# ARDUINO_3V_TTL_INTERFACE_2_PI.net
KiCad netlist of a schematic drawn in EAGLE
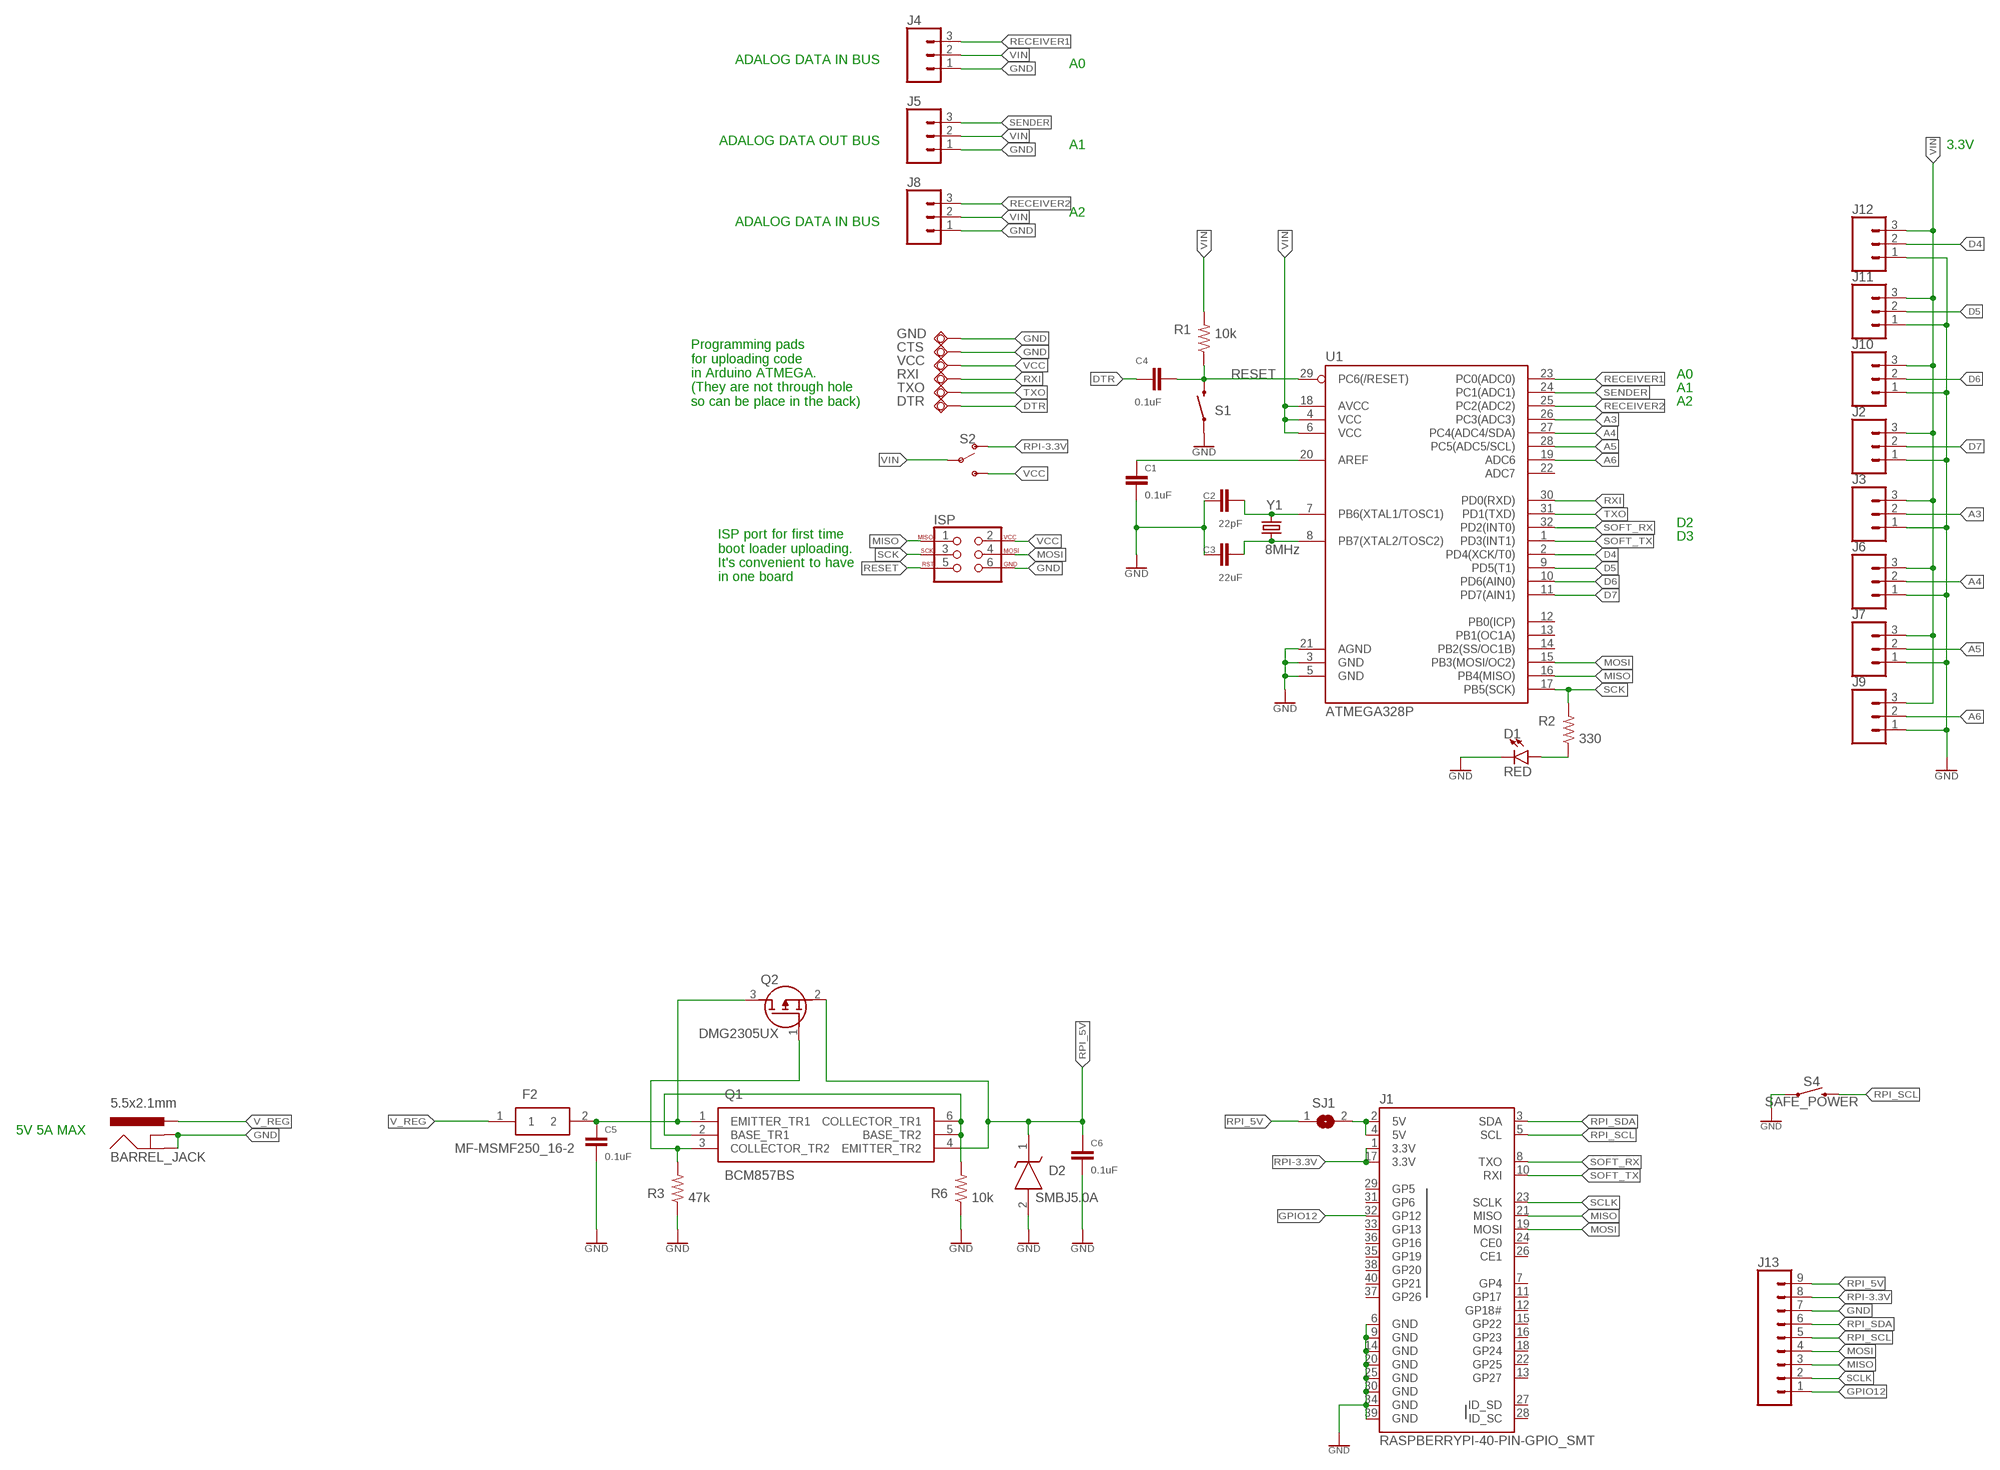
[diagram p0: schematic, sheet 1]

(export (version "E")
  (design (tool "Eeschema 10.0.6"))
  (components
    (comp (ref "BARREL_JACK")
      (value "5.5x2.1mm")
      (footprint "eagle-import:POWER_JACK_SMD")
      (libsource (lib "eagle-import") (part "POWER_JACKSMD"))
    )
    (comp (ref "C1")
      (value "0.1uF")
      (footprint "eagle-import:0603")
      (libsource (lib "eagle-import") (part "0.1UF-0603-100V-10%"))
    )
    (comp (ref "C2")
      (value "22pF")
      (footprint "eagle-import:0603")
      (libsource (lib "eagle-import") (part "0.1UF-0603-100V-10%"))
    )
    (comp (ref "C3")
      (value "22uF")
      (footprint "eagle-import:0603")
      (libsource (lib "eagle-import") (part "0.1UF-0603-100V-10%"))
    )
    (comp (ref "C4")
      (value "0.1uF")
      (footprint "eagle-import:0603")
      (libsource (lib "eagle-import") (part "0.1UF-0603-100V-10%"))
    )
    (comp (ref "C5")
      (value "0.1uF")
      (footprint "eagle-import:0603")
      (libsource (lib "eagle-import") (part "0.1UF-0603-100V-10%"))
    )
    (comp (ref "C6")
      (value "0.1uF")
      (footprint "eagle-import:0603")
      (libsource (lib "eagle-import") (part "0.1UF-0603-100V-10%"))
    )
    (comp (ref "CTS")
      (value "TPSQB1,27")
      (footprint "eagle-import:B1,27")
      (libsource (lib "eagle-import") (part "TPSQB1,27"))
    )
    (comp (ref "D1")
      (value "RED")
      (footprint "eagle-import:LED-0603")
      (libsource (lib "eagle-import") (part "LED-GREEN0603"))
    )
    (comp (ref "D2")
      (value "SMBJ5.0A")
      (footprint "eagle-import:DIOM5436X244N")
      (fields
        (field (name "MANUFACTURER_PART_NUMBER") "SMBJ5.0A-E3/52")
        (field (name "MOUSER_PART_NUMBER") "625-SMBJ5.0A-E3")
        (field (name "RS_PART_NUMBER") "1652507")
      )
      (libsource (lib "eagle-import") (part "SMBJ5.0A-E3_52"))
    )
    (comp (ref "DTR")
      (value "TPSQB1,27")
      (footprint "eagle-import:B1,27")
      (libsource (lib "eagle-import") (part "TPSQB1,27"))
    )
    (comp (ref "F2")
      (value "MF-MSMF250_16-2")
      (footprint "eagle-import:FUSC4632X160N")
      (fields
        (field (name "MANUFACTURER_PART_NUMBER") "MF-MSMF250/16-2")
        (field (name "MOUSER_PART_NUMBER") "652-MF-MSMF250/16-2")
      )
      (libsource (lib "eagle-import") (part "MF-MSMF250_16-2"))
    )
    (comp (ref "GND")
      (value "TPSQB1,27")
      (footprint "eagle-import:B1,27")
      (libsource (lib "eagle-import") (part "TPSQB1,27"))
    )
    (comp (ref "ISP")
      (value "AVR_SPI_PROG_3X2NS")
      (footprint "eagle-import:2X3-NS")
      (libsource (lib "eagle-import") (part "AVR_SPI_PROG_3X2NS"))
    )
    (comp (ref "J1")
      (value "RASPBERRYPI-40-PIN-GPIO_SMT")
      (footprint "eagle-import:2X20_SHROUDED_SMT")
      (libsource (lib "eagle-import") (part "RASPBERRYPI-40-PIN-GPIO_SMT"))
    )
    (comp (ref "J2")
      (value "CONN_03")
      (footprint "eagle-import:1X03")
      (libsource (lib "eagle-import") (part "CONN_03"))
    )
    (comp (ref "J3")
      (value "CONN_03")
      (footprint "eagle-import:1X03")
      (libsource (lib "eagle-import") (part "CONN_03"))
    )
    (comp (ref "J4")
      (value "CONN_03SMD")
      (footprint "eagle-import:1X03-1MM-RA")
      (libsource (lib "eagle-import") (part "CONN_03SMD"))
    )
    (comp (ref "J5")
      (value "CONN_03SMD")
      (footprint "eagle-import:1X03-1MM-RA")
      (libsource (lib "eagle-import") (part "CONN_03SMD"))
    )
    (comp (ref "J6")
      (value "CONN_03")
      (footprint "eagle-import:1X03")
      (libsource (lib "eagle-import") (part "CONN_03"))
    )
    (comp (ref "J7")
      (value "CONN_03")
      (footprint "eagle-import:1X03")
      (libsource (lib "eagle-import") (part "CONN_03"))
    )
    (comp (ref "J8")
      (value "CONN_03SMD")
      (footprint "eagle-import:1X03-1MM-RA")
      (libsource (lib "eagle-import") (part "CONN_03SMD"))
    )
    (comp (ref "J9")
      (value "CONN_03")
      (footprint "eagle-import:1X03")
      (libsource (lib "eagle-import") (part "CONN_03"))
    )
    (comp (ref "J10")
      (value "CONN_03")
      (footprint "eagle-import:1X03")
      (libsource (lib "eagle-import") (part "CONN_03"))
    )
    (comp (ref "J11")
      (value "CONN_03")
      (footprint "eagle-import:1X03")
      (libsource (lib "eagle-import") (part "CONN_03"))
    )
    (comp (ref "J12")
      (value "CONN_03")
      (footprint "eagle-import:1X03")
      (libsource (lib "eagle-import") (part "CONN_03"))
    )
    (comp (ref "J13")
      (value "CONN_09")
      (footprint "eagle-import:1X09")
      (libsource (lib "eagle-import") (part "CONN_09"))
    )
    (comp (ref "Q1")
      (value "BCM857BS")
      (footprint "eagle-import:SOT65P210X110-6N")
      (libsource (lib "eagle-import") (part "BCM857BS"))
    )
    (comp (ref "Q2")
      (value "DMG2305UX")
      (footprint "eagle-import:SOT96P240X102-3N")
      (fields
        (field (name "MANUFACTURER_PART_NUMBER") "DMG2305UXQ-7")
        (field (name "MOUSER_PART_NUMBER") "621-DMG2305UXQ-7")
      )
      (libsource (lib "eagle-import") (part "DMG2305UXQ-7"))
    )
    (comp (ref "R1")
      (value "10k")
      (footprint "eagle-import:0603")
      (libsource (lib "eagle-import") (part "10KOHM-0603-1/10W-1%"))
    )
    (comp (ref "R2")
      (value "330")
      (footprint "eagle-import:0603")
      (libsource (lib "eagle-import") (part "10KOHM-0603-1/10W-1%"))
    )
    (comp (ref "R3")
      (value "47k")
      (footprint "eagle-import:0603")
      (libsource (lib "eagle-import") (part "10KOHM-0603-1/10W-1%"))
    )
    (comp (ref "R6")
      (value "10k")
      (footprint "eagle-import:0603")
      (libsource (lib "eagle-import") (part "10KOHM-0603-1/10W-1%"))
    )
    (comp (ref "RXI")
      (value "TPSQB1,27")
      (footprint "eagle-import:B1,27")
      (libsource (lib "eagle-import") (part "TPSQB1,27"))
    )
    (comp (ref "S1")
      (value "RESET")
      (footprint "eagle-import:TACTILE_SWITCH_SMD_4.6X2.8MM")
      (libsource (lib "eagle-import") (part "MOMENTARY-SWITCH-SPST-SMD-4.6X2.8MM"))
    )
    (comp (ref "S2")
      (value "SWITCH-SPDT-SMD-RIGHT-ANGLE")
      (footprint "eagle-import:SWITCH_SPST_SMD_A")
      (libsource (lib "eagle-import") (part "SWITCH-SPDT-SMD-RIGHT-ANGLE"))
    )
    (comp (ref "S4")
      (value "SAFE_POWER")
      (footprint "eagle-import:TACTILE_SWITCH_PTH_12MM")
      (libsource (lib "eagle-import") (part "MOMENTARY-SWITCH-SPST-PTH-12MM"))
    )
    (comp (ref "SJ1") (value "SJ") (footprint "eagle-import:SJ") (libsource (lib "eagle-import") (part "SJ")))
    (comp (ref "TXO")
      (value "TPSQB1,27")
      (footprint "eagle-import:B1,27")
      (libsource (lib "eagle-import") (part "TPSQB1,27"))
    )
    (comp (ref "U1")
      (value "ATMEGA328P")
      (footprint "eagle-import:TQFP32-08")
      (libsource (lib "eagle-import") (part "ATMEGA328P_TQFP"))
    )
    (comp (ref "VCC")
      (value "TPSQB1,27")
      (footprint "eagle-import:B1,27")
      (libsource (lib "eagle-import") (part "TPSQB1,27"))
    )
    (comp (ref "Y1")
      (value "8MHz")
      (footprint "eagle-import:HC49UP")
      (libsource (lib "eagle-import") (part "CRYSTAL-8MHZSMD-HC49UP"))
    )
  )
  (nets
    (net (code "1") (name "A3") (class "Default")
      (node (ref "J3") (pin "2") (pinfunction "2_2") (pintype "passive"))
      (node (ref "U1") (pin "26") (pinfunction "PC3(ADC3)_26") (pintype "bidirectional"))
    )
    (net (code "2") (name "A4") (class "Default")
      (node (ref "J6") (pin "2") (pinfunction "2_2") (pintype "passive"))
      (node (ref "U1") (pin "27") (pinfunction "PC4(ADC4/SDA)_27") (pintype "bidirectional"))
    )
    (net (code "3") (name "A5") (class "Default")
      (node (ref "J7") (pin "2") (pinfunction "2_2") (pintype "passive"))
      (node (ref "U1") (pin "28") (pinfunction "PC5(ADC5/SCL)_28") (pintype "bidirectional"))
    )
    (net (code "4") (name "A6") (class "Default")
      (node (ref "J9") (pin "2") (pinfunction "2_2") (pintype "passive"))
      (node (ref "U1") (pin "19") (pinfunction "ADC6_19") (pintype "bidirectional"))
    )
    (net (code "5") (name "D4") (class "Default")
      (node (ref "J12") (pin "2") (pinfunction "2_2") (pintype "passive"))
      (node (ref "U1") (pin "2") (pinfunction "PD4(XCK/T0)_2") (pintype "bidirectional"))
    )
    (net (code "6") (name "D5") (class "Default")
      (node (ref "J11") (pin "2") (pinfunction "2_2") (pintype "passive"))
      (node (ref "U1") (pin "9") (pinfunction "PD5(T1)_9") (pintype "bidirectional"))
    )
    (net (code "7") (name "D6") (class "Default")
      (node (ref "J10") (pin "2") (pinfunction "2_2") (pintype "passive"))
      (node (ref "U1") (pin "10") (pinfunction "PD6(AIN0)_10") (pintype "bidirectional"))
    )
    (net (code "8") (name "D7") (class "Default")
      (node (ref "J2") (pin "2") (pinfunction "2_2") (pintype "passive"))
      (node (ref "U1") (pin "11") (pinfunction "PD7(AIN1)_11") (pintype "bidirectional"))
    )
    (net (code "9") (name "DTR") (class "Default")
      (node (ref "C4") (pin "1") (pinfunction "1_1") (pintype "passive"))
      (node (ref "DTR") (pin "TP") (pinfunction "TP_TP") (pintype "input"))
    )
    (net (code "10") (name "GND") (class "Default")
      (node (ref "BARREL_JACK") (pin "GND") (pinfunction "GNDBREAK_GND") (pintype "bidirectional"))
      (node (ref "BARREL_JACK") (pin "P$4") (pinfunction "GND_P$4") (pintype "bidirectional"))
      (node (ref "C1") (pin "2") (pinfunction "2_2") (pintype "passive"))
      (node (ref "C2") (pin "1") (pinfunction "1_1") (pintype "passive"))
      (node (ref "C3") (pin "1") (pinfunction "1_1") (pintype "passive"))
      (node (ref "C5") (pin "2") (pinfunction "2_2") (pintype "passive"))
      (node (ref "C6") (pin "2") (pinfunction "2_2") (pintype "passive"))
      (node (ref "CTS") (pin "TP") (pinfunction "TP_TP") (pintype "input"))
      (node (ref "D1") (pin "C") (pinfunction "C_C") (pintype "passive"))
      (node (ref "D2") (pin "2") (pinfunction "A_2") (pintype "bidirectional"))
      (node (ref "GND") (pin "TP") (pinfunction "TP_TP") (pintype "input"))
      (node (ref "ISP") (pin "6") (pinfunction "6_6") (pintype "passive"))
      (node (ref "J1") (pin "14") (pinfunction "GND_14") (pintype "power_in"))
      (node (ref "J1") (pin "20") (pinfunction "GND_20") (pintype "power_in"))
      (node (ref "J1") (pin "25") (pinfunction "GND_25") (pintype "power_in"))
      (node (ref "J1") (pin "30") (pinfunction "GND_30") (pintype "power_in"))
      (node (ref "J1") (pin "34") (pinfunction "GND_34") (pintype "power_in"))
      (node (ref "J1") (pin "39") (pinfunction "GND_39") (pintype "power_in"))
      (node (ref "J1") (pin "6") (pinfunction "GND_6") (pintype "power_in"))
      (node (ref "J1") (pin "9") (pinfunction "GND_9") (pintype "power_in"))
      (node (ref "J10") (pin "1") (pinfunction "1_1") (pintype "passive"))
      (node (ref "J11") (pin "1") (pinfunction "1_1") (pintype "passive"))
      (node (ref "J12") (pin "1") (pinfunction "1_1") (pintype "passive"))
      (node (ref "J13") (pin "7") (pinfunction "7_7") (pintype "passive"))
      (node (ref "J2") (pin "1") (pinfunction "1_1") (pintype "passive"))
      (node (ref "J3") (pin "1") (pinfunction "1_1") (pintype "passive"))
      (node (ref "J4") (pin "1") (pinfunction "1_1") (pintype "passive"))
      (node (ref "J5") (pin "1") (pinfunction "1_1") (pintype "passive"))
      (node (ref "J6") (pin "1") (pinfunction "1_1") (pintype "passive"))
      (node (ref "J7") (pin "1") (pinfunction "1_1") (pintype "passive"))
      (node (ref "J8") (pin "1") (pinfunction "1_1") (pintype "passive"))
      (node (ref "J9") (pin "1") (pinfunction "1_1") (pintype "passive"))
      (node (ref "R3") (pin "1") (pinfunction "1_1") (pintype "passive"))
      (node (ref "R6") (pin "1") (pinfunction "1_1") (pintype "passive"))
      (node (ref "S1") (pin "1") (pinfunction "1_1") (pintype "passive"))
      (node (ref "S1") (pin "2") (pinfunction "1_2") (pintype "passive"))
      (node (ref "S4") (pin "1") (pinfunction "1_1") (pintype "passive"))
      (node (ref "U1") (pin "21") (pinfunction "AGND_21") (pintype "bidirectional"))
      (node (ref "U1") (pin "3") (pinfunction "GND_3") (pintype "bidirectional"))
      (node (ref "U1") (pin "5") (pinfunction "GND_5") (pintype "bidirectional"))
    )
    (net (code "11") (name "GPIO12") (class "Default")
      (node (ref "J1") (pin "32") (pinfunction "GP12_32") (pintype "bidirectional"))
      (node (ref "J13") (pin "1") (pinfunction "1_1") (pintype "passive"))
    )
    (net (code "12") (name "MISO") (class "Default")
      (node (ref "ISP") (pin "1") (pinfunction "1_1") (pintype "passive"))
      (node (ref "J1") (pin "21") (pinfunction "MISO_21") (pintype "input"))
      (node (ref "J13") (pin "3") (pinfunction "3_3") (pintype "passive"))
      (node (ref "U1") (pin "16") (pinfunction "PB4(MISO)_16") (pintype "bidirectional"))
    )
    (net (code "13") (name "MOSI") (class "Default")
      (node (ref "ISP") (pin "4") (pinfunction "4_4") (pintype "passive"))
      (node (ref "J1") (pin "19") (pinfunction "MOSI_19") (pintype "output"))
      (node (ref "J13") (pin "4") (pinfunction "4_4") (pintype "passive"))
      (node (ref "U1") (pin "15") (pinfunction "PB3(MOSI/OC2)_15") (pintype "bidirectional"))
    )
    (net (code "14") (name "Net-(D1-PadA)") (class "Default")
      (node (ref "D1") (pin "A") (pinfunction "A_A") (pintype "passive"))
      (node (ref "R2") (pin "1") (pinfunction "1_1") (pintype "passive"))
    )
    (net (code "15") (name "Net-(J1-5V-Pad2)") (class "Default")
      (node (ref "J1") (pin "2") (pinfunction "5V_2") (pintype "power_in"))
      (node (ref "J1") (pin "4") (pinfunction "5V_4") (pintype "power_in"))
      (node (ref "SJ1") (pin "2") (pinfunction "2_2") (pintype "passive"))
    )
    (net (code "16") (name "Net-(Q1-BASE_TR1)") (class "Default")
      (node (ref "Q1") (pin "2") (pinfunction "BASE_TR1_2") (pintype "bidirectional"))
      (node (ref "Q1") (pin "5") (pinfunction "BASE_TR2_5") (pintype "bidirectional"))
      (node (ref "Q1") (pin "6") (pinfunction "COLLECTOR_TR1_6") (pintype "bidirectional"))
      (node (ref "R6") (pin "2") (pinfunction "2_2") (pintype "passive"))
    )
    (net (code "17") (name "Net-(Q1-COLLECTOR_TR2)") (class "Default")
      (node (ref "Q1") (pin "3") (pinfunction "COLLECTOR_TR2_3") (pintype "bidirectional"))
      (node (ref "Q2") (pin "1") (pinfunction "G_1") (pintype "input"))
      (node (ref "R3") (pin "2") (pinfunction "2_2") (pintype "passive"))
    )
    (net (code "18") (name "Net-(U1-AREF)") (class "Default")
      (node (ref "C1") (pin "1") (pinfunction "1_1") (pintype "passive"))
      (node (ref "U1") (pin "20") (pinfunction "AREF_20") (pintype "bidirectional"))
    )
    (net (code "19") (name "Net-(U1-PB6(XTAL1{slash}TOSC1))") (class "Default")
      (node (ref "C2") (pin "2") (pinfunction "2_2") (pintype "passive"))
      (node (ref "U1") (pin "7") (pinfunction "PB6(XTAL1/TOSC1)_7") (pintype "bidirectional"))
      (node (ref "Y1") (pin "2") (pinfunction "2_2") (pintype "passive"))
    )
    (net (code "20") (name "Net-(U1-PB7(XTAL2{slash}TOSC2))") (class "Default")
      (node (ref "C3") (pin "2") (pinfunction "2_2") (pintype "passive"))
      (node (ref "U1") (pin "8") (pinfunction "PB7(XTAL2/TOSC2)_8") (pintype "bidirectional"))
      (node (ref "Y1") (pin "1") (pinfunction "1_1") (pintype "passive"))
    )
    (net (code "21") (name "RECEIVER1") (class "Default")
      (node (ref "J4") (pin "3") (pinfunction "3_3") (pintype "passive"))
      (node (ref "U1") (pin "23") (pinfunction "PC0(ADC0)_23") (pintype "bidirectional"))
    )
    (net (code "22") (name "RECEIVER2") (class "Default")
      (node (ref "J8") (pin "3") (pinfunction "3_3") (pintype "passive"))
      (node (ref "U1") (pin "25") (pinfunction "PC2(ADC2)_25") (pintype "bidirectional"))
    )
    (net (code "23") (name "RESET") (class "Default")
      (node (ref "C4") (pin "2") (pinfunction "2_2") (pintype "passive"))
      (node (ref "ISP") (pin "5") (pinfunction "5_5") (pintype "passive"))
      (node (ref "R1") (pin "1") (pinfunction "1_1") (pintype "passive"))
      (node (ref "S1") (pin "3") (pinfunction "2_3") (pintype "passive"))
      (node (ref "S1") (pin "4") (pinfunction "2_4") (pintype "passive"))
      (node (ref "U1") (pin "29") (pinfunction "PC6(/RESET)_29") (pintype "bidirectional"))
    )
    (net (code "24") (name "RPI-3.3V") (class "Default")
      (node (ref "J1") (pin "1") (pinfunction "3.3V_1") (pintype "power_in"))
      (node (ref "J1") (pin "17") (pinfunction "3.3V_17") (pintype "power_in"))
      (node (ref "J13") (pin "8") (pinfunction "8_8") (pintype "passive"))
      (node (ref "S2") (pin "1") (pinfunction "O_1") (pintype "passive"))
    )
    (net (code "25") (name "RPI_5V") (class "Default")
      (node (ref "C6") (pin "1") (pinfunction "1_1") (pintype "passive"))
      (node (ref "D2") (pin "1") (pinfunction "K_1") (pintype "bidirectional"))
      (node (ref "J13") (pin "9") (pinfunction "9_9") (pintype "passive"))
      (node (ref "Q1") (pin "4") (pinfunction "EMITTER_TR2_4") (pintype "bidirectional"))
      (node (ref "Q2") (pin "2") (pinfunction "S_2") (pintype "bidirectional"))
      (node (ref "SJ1") (pin "1") (pinfunction "1_1") (pintype "passive"))
    )
    (net (code "26") (name "RPI_SCL") (class "Default")
      (node (ref "J1") (pin "5") (pinfunction "SCL_5") (pintype "bidirectional"))
      (node (ref "J13") (pin "5") (pinfunction "5_5") (pintype "passive"))
      (node (ref "S4") (pin "3") (pinfunction "2_3") (pintype "passive"))
    )
    (net (code "27") (name "RPI_SDA") (class "Default")
      (node (ref "J1") (pin "3") (pinfunction "SDA_3") (pintype "bidirectional"))
      (node (ref "J13") (pin "6") (pinfunction "6_6") (pintype "passive"))
    )
    (net (code "28") (name "RXI") (class "Default")
      (node (ref "RXI") (pin "TP") (pinfunction "TP_TP") (pintype "input"))
      (node (ref "U1") (pin "30") (pinfunction "PD0(RXD)_30") (pintype "bidirectional"))
    )
    (net (code "29") (name "SCK") (class "Default")
      (node (ref "ISP") (pin "3") (pinfunction "3_3") (pintype "passive"))
      (node (ref "R2") (pin "2") (pinfunction "2_2") (pintype "passive"))
      (node (ref "U1") (pin "17") (pinfunction "PB5(SCK)_17") (pintype "bidirectional"))
    )
    (net (code "30") (name "SCLK") (class "Default")
      (node (ref "J1") (pin "23") (pinfunction "SCLK_23") (pintype "output"))
      (node (ref "J13") (pin "2") (pinfunction "2_2") (pintype "passive"))
    )
    (net (code "31") (name "SENDER") (class "Default")
      (node (ref "J5") (pin "3") (pinfunction "3_3") (pintype "passive"))
      (node (ref "U1") (pin "24") (pinfunction "PC1(ADC1)_24") (pintype "bidirectional"))
    )
    (net (code "32") (name "SOFT_RX") (class "Default")
      (node (ref "J1") (pin "8") (pinfunction "TXO_8") (pintype "output"))
      (node (ref "U1") (pin "32") (pinfunction "PD2(INT0)_32") (pintype "bidirectional"))
    )
    (net (code "33") (name "SOFT_TX") (class "Default")
      (node (ref "J1") (pin "10") (pinfunction "RXI_10") (pintype "input"))
      (node (ref "U1") (pin "1") (pinfunction "PD3(INT1)_1") (pintype "bidirectional"))
    )
    (net (code "34") (name "TXO") (class "Default")
      (node (ref "TXO") (pin "TP") (pinfunction "TP_TP") (pintype "input"))
      (node (ref "U1") (pin "31") (pinfunction "PD1(TXD)_31") (pintype "bidirectional"))
    )
    (net (code "35") (name "VCC") (class "Default")
      (node (ref "ISP") (pin "2") (pinfunction "2_2") (pintype "passive"))
      (node (ref "S2") (pin "3") (pinfunction "S_3") (pintype "passive"))
      (node (ref "VCC") (pin "TP") (pinfunction "TP_TP") (pintype "input"))
    )
    (net (code "36") (name "VIN") (class "Default")
      (node (ref "J10") (pin "3") (pinfunction "3_3") (pintype "passive"))
      (node (ref "J11") (pin "3") (pinfunction "3_3") (pintype "passive"))
      (node (ref "J12") (pin "3") (pinfunction "3_3") (pintype "passive"))
      (node (ref "J2") (pin "3") (pinfunction "3_3") (pintype "passive"))
      (node (ref "J3") (pin "3") (pinfunction "3_3") (pintype "passive"))
      (node (ref "J4") (pin "2") (pinfunction "2_2") (pintype "passive"))
      (node (ref "J5") (pin "2") (pinfunction "2_2") (pintype "passive"))
      (node (ref "J6") (pin "3") (pinfunction "3_3") (pintype "passive"))
      (node (ref "J7") (pin "3") (pinfunction "3_3") (pintype "passive"))
      (node (ref "J8") (pin "2") (pinfunction "2_2") (pintype "passive"))
      (node (ref "J9") (pin "3") (pinfunction "3_3") (pintype "passive"))
      (node (ref "R1") (pin "2") (pinfunction "2_2") (pintype "passive"))
      (node (ref "S2") (pin "2") (pinfunction "P_2") (pintype "passive"))
      (node (ref "U1") (pin "18") (pinfunction "AVCC_18") (pintype "bidirectional"))
      (node (ref "U1") (pin "4") (pinfunction "VCC_4") (pintype "bidirectional"))
      (node (ref "U1") (pin "6") (pinfunction "VCC_6") (pintype "bidirectional"))
    )
    (net (code "37") (name "V_REG") (class "Default")
      (node (ref "BARREL_JACK") (pin "VIN0") (pinfunction "PWR_VIN0") (pintype "bidirectional"))
      (node (ref "C5") (pin "1") (pinfunction "1_1") (pintype "passive"))
      (node (ref "F2") (pin "1") (pinfunction "1_1") (pintype "bidirectional"))
      (node (ref "F2") (pin "2") (pinfunction "2_2") (pintype "bidirectional"))
      (node (ref "Q1") (pin "1") (pinfunction "EMITTER_TR1_1") (pintype "bidirectional"))
      (node (ref "Q2") (pin "3") (pinfunction "D_3") (pintype "bidirectional"))
    )
    (net (code "38") (name "unconnected-(J1-CE0-Pad24)") (class "Default")
      (node (ref "J1") (pin "24") (pinfunction "CE0_24") (pintype "output"))
    )
    (net (code "39") (name "unconnected-(J1-CE1-Pad26)") (class "Default")
      (node (ref "J1") (pin "26") (pinfunction "CE1_26") (pintype "output"))
    )
    (net (code "40") (name "unconnected-(J1-GP4-Pad7)") (class "Default")
      (node (ref "J1") (pin "7") (pinfunction "GP4_7") (pintype "bidirectional"))
    )
    (net (code "41") (name "unconnected-(J1-GP5-Pad29)") (class "Default")
      (node (ref "J1") (pin "29") (pinfunction "GP5_29") (pintype "bidirectional"))
    )
    (net (code "42") (name "unconnected-(J1-GP6-Pad31)") (class "Default")
      (node (ref "J1") (pin "31") (pinfunction "GP6_31") (pintype "bidirectional"))
    )
    (net (code "43") (name "unconnected-(J1-GP13-Pad33)") (class "Default")
      (node (ref "J1") (pin "33") (pinfunction "GP13_33") (pintype "bidirectional"))
    )
    (net (code "44") (name "unconnected-(J1-GP16-Pad36)") (class "Default")
      (node (ref "J1") (pin "36") (pinfunction "GP16_36") (pintype "bidirectional"))
    )
    (net (code "45") (name "unconnected-(J1-GP17-Pad11)") (class "Default")
      (node (ref "J1") (pin "11") (pinfunction "GP17_11") (pintype "bidirectional"))
    )
    (net (code "46") (name "unconnected-(J1-GP18#-Pad12)") (class "Default")
      (node (ref "J1") (pin "12") (pinfunction "GP18#_12") (pintype "bidirectional"))
    )
    (net (code "47") (name "unconnected-(J1-GP19-Pad35)") (class "Default")
      (node (ref "J1") (pin "35") (pinfunction "GP19_35") (pintype "bidirectional"))
    )
    (net (code "48") (name "unconnected-(J1-GP20-Pad38)") (class "Default")
      (node (ref "J1") (pin "38") (pinfunction "GP20_38") (pintype "bidirectional"))
    )
    (net (code "49") (name "unconnected-(J1-GP21-Pad40)") (class "Default")
      (node (ref "J1") (pin "40") (pinfunction "GP21_40") (pintype "bidirectional"))
    )
    (net (code "50") (name "unconnected-(J1-GP22-Pad15)") (class "Default")
      (node (ref "J1") (pin "15") (pinfunction "GP22_15") (pintype "bidirectional"))
    )
    (net (code "51") (name "unconnected-(J1-GP23-Pad16)") (class "Default")
      (node (ref "J1") (pin "16") (pinfunction "GP23_16") (pintype "bidirectional"))
    )
    (net (code "52") (name "unconnected-(J1-GP24-Pad18)") (class "Default")
      (node (ref "J1") (pin "18") (pinfunction "GP24_18") (pintype "bidirectional"))
    )
    (net (code "53") (name "unconnected-(J1-GP25-Pad22)") (class "Default")
      (node (ref "J1") (pin "22") (pinfunction "GP25_22") (pintype "bidirectional"))
    )
    (net (code "54") (name "unconnected-(J1-GP26-Pad37)") (class "Default")
      (node (ref "J1") (pin "37") (pinfunction "GP26_37") (pintype "bidirectional"))
    )
    (net (code "55") (name "unconnected-(J1-GP27-Pad13)") (class "Default")
      (node (ref "J1") (pin "13") (pinfunction "GP27_13") (pintype "bidirectional"))
    )
    (net (code "56") (name "unconnected-(J1-ID_SC-Pad28)") (class "Default")
      (node (ref "J1") (pin "28") (pinfunction "ID_SC_28") (pintype "bidirectional"))
    )
    (net (code "57") (name "unconnected-(J1-ID_SD-Pad27)") (class "Default")
      (node (ref "J1") (pin "27") (pinfunction "ID_SD_27") (pintype "bidirectional"))
    )
    (net (code "58") (name "unconnected-(U1-ADC7-Pad22)") (class "Default")
      (node (ref "U1") (pin "22") (pinfunction "ADC7_22") (pintype "bidirectional"))
    )
    (net (code "59") (name "unconnected-(U1-PB0(ICP)-Pad12)") (class "Default")
      (node (ref "U1") (pin "12") (pinfunction "PB0(ICP)_12") (pintype "bidirectional"))
    )
    (net (code "60") (name "unconnected-(U1-PB1(OC1A)-Pad13)") (class "Default")
      (node (ref "U1") (pin "13") (pinfunction "PB1(OC1A)_13") (pintype "bidirectional"))
    )
    (net (code "61") (name "unconnected-(U1-PB2(SS{slash}OC1B)-Pad14)") (class "Default")
      (node (ref "U1") (pin "14") (pinfunction "PB2(SS/OC1B)_14") (pintype "bidirectional"))
    )
  )
)
